# untitled_2.net
KiCad netlist of a schematic drawn in EAGLE
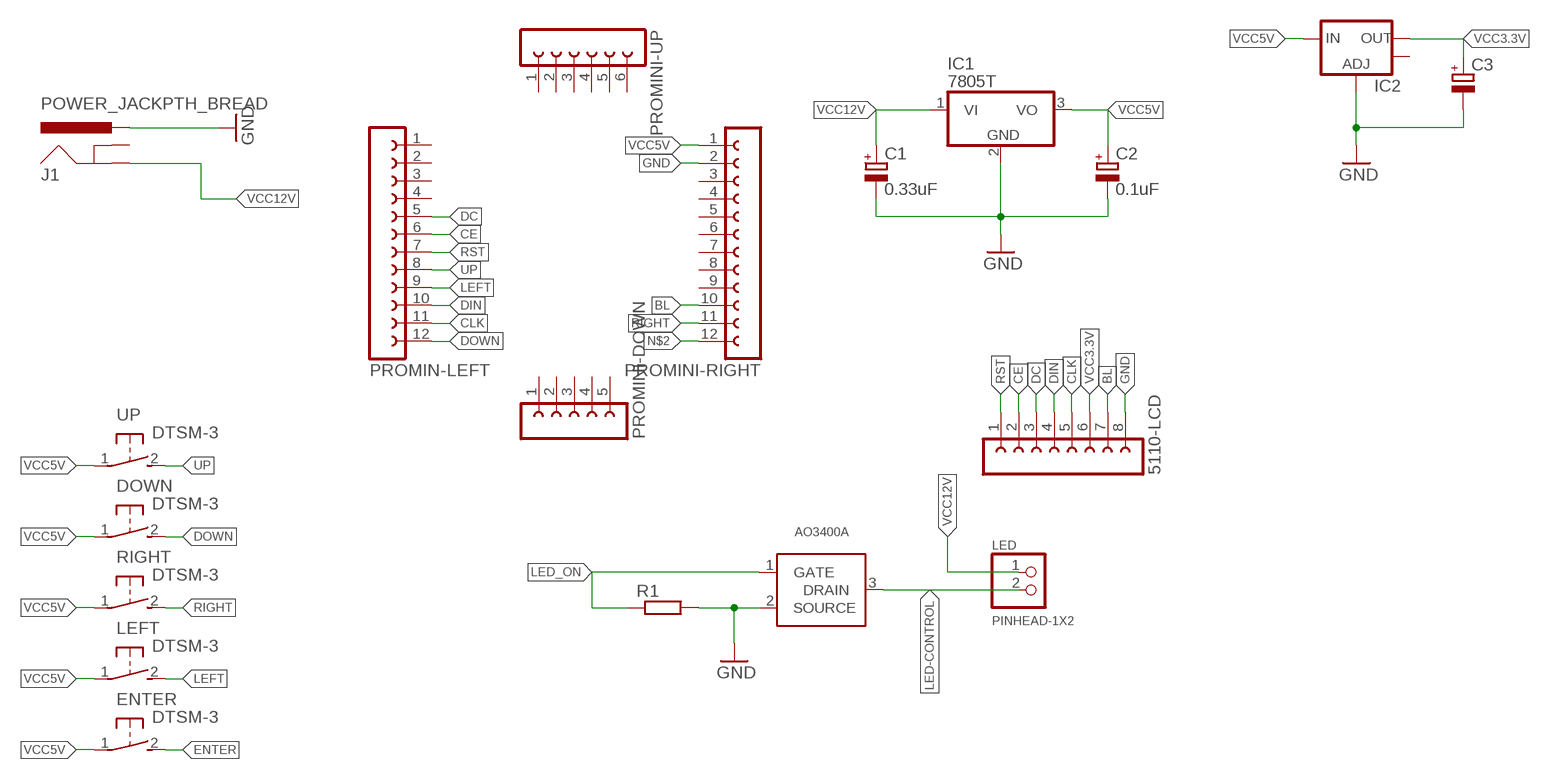
[diagram p0: schematic, sheet 1]

(export (version "E")
  (design (tool "Eeschema 10.0.6"))
  (components
    (comp (ref "5110-LCD")
      (value "FE08-1")
      (footprint "eagle-import:FE08")
      (libsource (lib "eagle-import") (part "FE08-1"))
    )
    (comp (ref "C1")
      (value "0.33uF")
      (footprint "eagle-import:E1,8-4")
      (libsource (lib "eagle-import") (part "CPOL-EUE1.8-4"))
    )
    (comp (ref "C2")
      (value "0.1uF")
      (footprint "eagle-import:E1,8-4")
      (libsource (lib "eagle-import") (part "CPOL-EUE1.8-4"))
    )
    (comp (ref "C3")
      (value "CPOL-EUE1.8-4")
      (footprint "eagle-import:E1,8-4")
      (libsource (lib "eagle-import") (part "CPOL-EUE1.8-4"))
    )
    (comp (ref "DOWN")
      (value "DTSM-3")
      (footprint "eagle-import:DTSM-3")
      (libsource (lib "eagle-import") (part "DTSM-3"))
    )
    (comp (ref "ENTER")
      (value "DTSM-3")
      (footprint "eagle-import:DTSM-3")
      (libsource (lib "eagle-import") (part "DTSM-3"))
    )
    (comp (ref "IC1")
      (value "7805T")
      (footprint "eagle-import:TO220H")
      (libsource (lib "eagle-import") (part "78T05"))
    )
    (comp (ref "IC2")
      (value "V_REG_LM1117SOT223")
      (footprint "eagle-import:SOT223")
      (libsource (lib "eagle-import") (part "V_REG_LM1117SOT223"))
    )
    (comp (ref "J1")
      (value "POWER_JACKPTH_BREAD")
      (footprint "eagle-import:POWER_JACK_PTH_BREAD")
      (libsource (lib "eagle-import") (part "POWER_JACKPTH_BREAD"))
    )
    (comp (ref "LED")
      (value "PINHEAD-1X2")
      (footprint "eagle-import:PIHEAD-1X2")
      (libsource (lib "eagle-import") (part "PINHEAD-1X2"))
    )
    (comp (ref "LEFT")
      (value "DTSM-3")
      (footprint "eagle-import:DTSM-3")
      (libsource (lib "eagle-import") (part "DTSM-3"))
    )
    (comp (ref "PROMIN-LEFT")
      (value "FE12-1")
      (footprint "eagle-import:FE12")
      (libsource (lib "eagle-import") (part "FE12-1"))
    )
    (comp (ref "PROMINI-DOWN")
      (value "FE05-1")
      (footprint "eagle-import:FE05-1")
      (libsource (lib "eagle-import") (part "FE05-1"))
    )
    (comp (ref "PROMINI-RIGHT")
      (value "FE12-1")
      (footprint "eagle-import:FE12")
      (libsource (lib "eagle-import") (part "FE12-1"))
    )
    (comp (ref "PROMINI-UP")
      (value "FE06-1")
      (footprint "eagle-import:FE06")
      (libsource (lib "eagle-import") (part "FE06-1"))
    )
    (comp (ref "R1")
      (value "R-EU_R1206")
      (footprint "eagle-import:R1206")
      (libsource (lib "eagle-import") (part "R-EU_R1206"))
    )
    (comp (ref "RIGHT")
      (value "DTSM-3")
      (footprint "eagle-import:DTSM-3")
      (libsource (lib "eagle-import") (part "DTSM-3"))
    )
    (comp (ref "U$1")
      (value "AO3400A")
      (footprint "eagle-import:SOT-23")
      (libsource (lib "eagle-import") (part "AO3400A"))
    )
    (comp (ref "UP")
      (value "DTSM-3")
      (footprint "eagle-import:DTSM-3")
      (libsource (lib "eagle-import") (part "DTSM-3"))
    )
  )
  (nets
    (net (code "1") (name "BL") (class "Default")
      (node (ref "5110-LCD") (pin "7") (pinfunction "7_7") (pintype "passive"))
      (node (ref "PROMINI-RIGHT") (pin "10") (pinfunction "10_10") (pintype "passive"))
    )
    (net (code "2") (name "CE") (class "Default")
      (node (ref "5110-LCD") (pin "2") (pinfunction "2_2") (pintype "passive"))
      (node (ref "PROMIN-LEFT") (pin "6") (pinfunction "6_6") (pintype "passive"))
    )
    (net (code "3") (name "CLK") (class "Default")
      (node (ref "5110-LCD") (pin "5") (pinfunction "5_5") (pintype "passive"))
      (node (ref "PROMIN-LEFT") (pin "11") (pinfunction "11_11") (pintype "passive"))
    )
    (net (code "4") (name "DC") (class "Default")
      (node (ref "5110-LCD") (pin "3") (pinfunction "3_3") (pintype "passive"))
      (node (ref "PROMIN-LEFT") (pin "5") (pinfunction "5_5") (pintype "passive"))
    )
    (net (code "5") (name "DIN") (class "Default")
      (node (ref "5110-LCD") (pin "4") (pinfunction "4_4") (pintype "passive"))
      (node (ref "PROMIN-LEFT") (pin "10") (pinfunction "10_10") (pintype "passive"))
    )
    (net (code "6") (name "DOWN") (class "Default")
      (node (ref "DOWN") (pin "2") (pinfunction "2_2") (pintype "passive"))
      (node (ref "PROMIN-LEFT") (pin "12") (pinfunction "12_12") (pintype "passive"))
    )
    (net (code "7") (name "ENTER") (class "Default")
      (node (ref "ENTER") (pin "2") (pinfunction "2_2") (pintype "passive"))
    )
    (net (code "8") (name "GND") (class "Default")
      (node (ref "5110-LCD") (pin "8") (pinfunction "8_8") (pintype "passive"))
      (node (ref "C1") (pin "-") (pinfunction "-_-") (pintype "passive"))
      (node (ref "C2") (pin "-") (pinfunction "-_-") (pintype "passive"))
      (node (ref "C3") (pin "-") (pinfunction "-_-") (pintype "passive"))
      (node (ref "IC1") (pin "2") (pinfunction "GND_2") (pintype "passive"))
      (node (ref "IC2") (pin "1") (pinfunction "ADJ_1") (pintype "input"))
      (node (ref "J1") (pin "PWR") (pinfunction "PWR_PWR") (pintype "bidirectional"))
      (node (ref "PROMINI-RIGHT") (pin "2") (pinfunction "2_2") (pintype "passive"))
      (node (ref "R1") (pin "2") (pinfunction "2_2") (pintype "passive"))
      (node (ref "U$1") (pin "2") (pinfunction "SOURCE_2") (pintype "bidirectional"))
    )
    (net (code "9") (name "LED-CONTROL") (class "Default")
      (node (ref "LED") (pin "2") (pinfunction "2_2") (pintype "passive"))
      (node (ref "U$1") (pin "3") (pinfunction "DRAIN_3") (pintype "bidirectional"))
    )
    (net (code "10") (name "LED_ON") (class "Default")
      (node (ref "R1") (pin "1") (pinfunction "1_1") (pintype "passive"))
      (node (ref "U$1") (pin "1") (pinfunction "GATE_1") (pintype "bidirectional"))
    )
    (net (code "11") (name "LEFT") (class "Default")
      (node (ref "LEFT") (pin "2") (pinfunction "2_2") (pintype "passive"))
      (node (ref "PROMIN-LEFT") (pin "9") (pinfunction "9_9") (pintype "passive"))
    )
    (net (code "12") (name "N$2") (class "Default")
      (node (ref "PROMINI-RIGHT") (pin "12") (pinfunction "12_12") (pintype "passive"))
    )
    (net (code "13") (name "RIGHT") (class "Default")
      (node (ref "PROMINI-RIGHT") (pin "11") (pinfunction "11_11") (pintype "passive"))
      (node (ref "RIGHT") (pin "2") (pinfunction "2_2") (pintype "passive"))
    )
    (net (code "14") (name "RST") (class "Default")
      (node (ref "5110-LCD") (pin "1") (pinfunction "1_1") (pintype "passive"))
      (node (ref "PROMIN-LEFT") (pin "7") (pinfunction "7_7") (pintype "passive"))
    )
    (net (code "15") (name "UP") (class "Default")
      (node (ref "PROMIN-LEFT") (pin "8") (pinfunction "8_8") (pintype "passive"))
      (node (ref "UP") (pin "2") (pinfunction "2_2") (pintype "passive"))
    )
    (net (code "16") (name "VCC3.3V") (class "Default")
      (node (ref "5110-LCD") (pin "6") (pinfunction "6_6") (pintype "passive"))
      (node (ref "C3") (pin "+") (pinfunction "+_+") (pintype "passive"))
      (node (ref "IC2") (pin "2") (pinfunction "OUT_2") (pintype "output"))
    )
    (net (code "17") (name "VCC5V") (class "Default")
      (node (ref "C2") (pin "+") (pinfunction "+_+") (pintype "passive"))
      (node (ref "DOWN") (pin "1") (pinfunction "1_1") (pintype "passive"))
      (node (ref "ENTER") (pin "1") (pinfunction "1_1") (pintype "passive"))
      (node (ref "IC1") (pin "3") (pinfunction "VO_3") (pintype "passive"))
      (node (ref "IC2") (pin "3") (pinfunction "IN_3") (pintype "input"))
      (node (ref "LEFT") (pin "1") (pinfunction "1_1") (pintype "passive"))
      (node (ref "PROMINI-RIGHT") (pin "1") (pinfunction "1_1") (pintype "passive"))
      (node (ref "RIGHT") (pin "1") (pinfunction "1_1") (pintype "passive"))
      (node (ref "UP") (pin "1") (pinfunction "1_1") (pintype "passive"))
    )
    (net (code "18") (name "VCC12V") (class "Default")
      (node (ref "C1") (pin "+") (pinfunction "+_+") (pintype "passive"))
      (node (ref "IC1") (pin "1") (pinfunction "VI_1") (pintype "input"))
      (node (ref "J1") (pin "GND") (pinfunction "GND_GND") (pintype "bidirectional"))
      (node (ref "LED") (pin "1") (pinfunction "1_1") (pintype "passive"))
    )
    (net (code "19") (name "unconnected-(IC2-OUT-Pad4)") (class "Default")
      (node (ref "IC2") (pin "4") (pinfunction "OUT_4") (pintype "output"))
    )
    (net (code "20") (name "unconnected-(J1-PadGNDBREAK)") (class "Default")
      (node (ref "J1") (pin "GNDBREAK") (pinfunction "GNDBREAK_GNDBREAK") (pintype "bidirectional"))
    )
    (net (code "21") (name "unconnected-(PROMIN-LEFT-Pad1)") (class "Default")
      (node (ref "PROMIN-LEFT") (pin "1") (pinfunction "1_1") (pintype "passive"))
    )
    (net (code "22") (name "unconnected-(PROMIN-LEFT-Pad2)") (class "Default")
      (node (ref "PROMIN-LEFT") (pin "2") (pinfunction "2_2") (pintype "passive"))
    )
    (net (code "23") (name "unconnected-(PROMIN-LEFT-Pad3)") (class "Default")
      (node (ref "PROMIN-LEFT") (pin "3") (pinfunction "3_3") (pintype "passive"))
    )
    (net (code "24") (name "unconnected-(PROMIN-LEFT-Pad4)") (class "Default")
      (node (ref "PROMIN-LEFT") (pin "4") (pinfunction "4_4") (pintype "passive"))
    )
    (net (code "25") (name "unconnected-(PROMINI-DOWN-Pad1)") (class "Default")
      (node (ref "PROMINI-DOWN") (pin "1") (pinfunction "1_1") (pintype "passive"))
    )
    (net (code "26") (name "unconnected-(PROMINI-DOWN-Pad2)") (class "Default")
      (node (ref "PROMINI-DOWN") (pin "2") (pinfunction "2_2") (pintype "passive"))
    )
    (net (code "27") (name "unconnected-(PROMINI-DOWN-Pad3)") (class "Default")
      (node (ref "PROMINI-DOWN") (pin "3") (pinfunction "3_3") (pintype "passive"))
    )
    (net (code "28") (name "unconnected-(PROMINI-DOWN-Pad4)") (class "Default")
      (node (ref "PROMINI-DOWN") (pin "4") (pinfunction "4_4") (pintype "passive"))
    )
    (net (code "29") (name "unconnected-(PROMINI-DOWN-Pad5)") (class "Default")
      (node (ref "PROMINI-DOWN") (pin "5") (pinfunction "5_5") (pintype "passive"))
    )
    (net (code "30") (name "unconnected-(PROMINI-RIGHT-Pad3)") (class "Default")
      (node (ref "PROMINI-RIGHT") (pin "3") (pinfunction "3_3") (pintype "passive"))
    )
    (net (code "31") (name "unconnected-(PROMINI-RIGHT-Pad4)") (class "Default")
      (node (ref "PROMINI-RIGHT") (pin "4") (pinfunction "4_4") (pintype "passive"))
    )
    (net (code "32") (name "unconnected-(PROMINI-RIGHT-Pad5)") (class "Default")
      (node (ref "PROMINI-RIGHT") (pin "5") (pinfunction "5_5") (pintype "passive"))
    )
    (net (code "33") (name "unconnected-(PROMINI-RIGHT-Pad6)") (class "Default")
      (node (ref "PROMINI-RIGHT") (pin "6") (pinfunction "6_6") (pintype "passive"))
    )
    (net (code "34") (name "unconnected-(PROMINI-RIGHT-Pad7)") (class "Default")
      (node (ref "PROMINI-RIGHT") (pin "7") (pinfunction "7_7") (pintype "passive"))
    )
    (net (code "35") (name "unconnected-(PROMINI-RIGHT-Pad8)") (class "Default")
      (node (ref "PROMINI-RIGHT") (pin "8") (pinfunction "8_8") (pintype "passive"))
    )
    (net (code "36") (name "unconnected-(PROMINI-RIGHT-Pad9)") (class "Default")
      (node (ref "PROMINI-RIGHT") (pin "9") (pinfunction "9_9") (pintype "passive"))
    )
    (net (code "37") (name "unconnected-(PROMINI-UP-Pad1)") (class "Default")
      (node (ref "PROMINI-UP") (pin "1") (pinfunction "1_1") (pintype "passive"))
    )
    (net (code "38") (name "unconnected-(PROMINI-UP-Pad2)") (class "Default")
      (node (ref "PROMINI-UP") (pin "2") (pinfunction "2_2") (pintype "passive"))
    )
    (net (code "39") (name "unconnected-(PROMINI-UP-Pad3)") (class "Default")
      (node (ref "PROMINI-UP") (pin "3") (pinfunction "3_3") (pintype "passive"))
    )
    (net (code "40") (name "unconnected-(PROMINI-UP-Pad4)") (class "Default")
      (node (ref "PROMINI-UP") (pin "4") (pinfunction "4_4") (pintype "passive"))
    )
    (net (code "41") (name "unconnected-(PROMINI-UP-Pad5)") (class "Default")
      (node (ref "PROMINI-UP") (pin "5") (pinfunction "5_5") (pintype "passive"))
    )
    (net (code "42") (name "unconnected-(PROMINI-UP-Pad6)") (class "Default")
      (node (ref "PROMINI-UP") (pin "6") (pinfunction "6_6") (pintype "passive"))
    )
  )
)
